# cc2510.net
KiCad netlist of a schematic drawn in Altium Designer
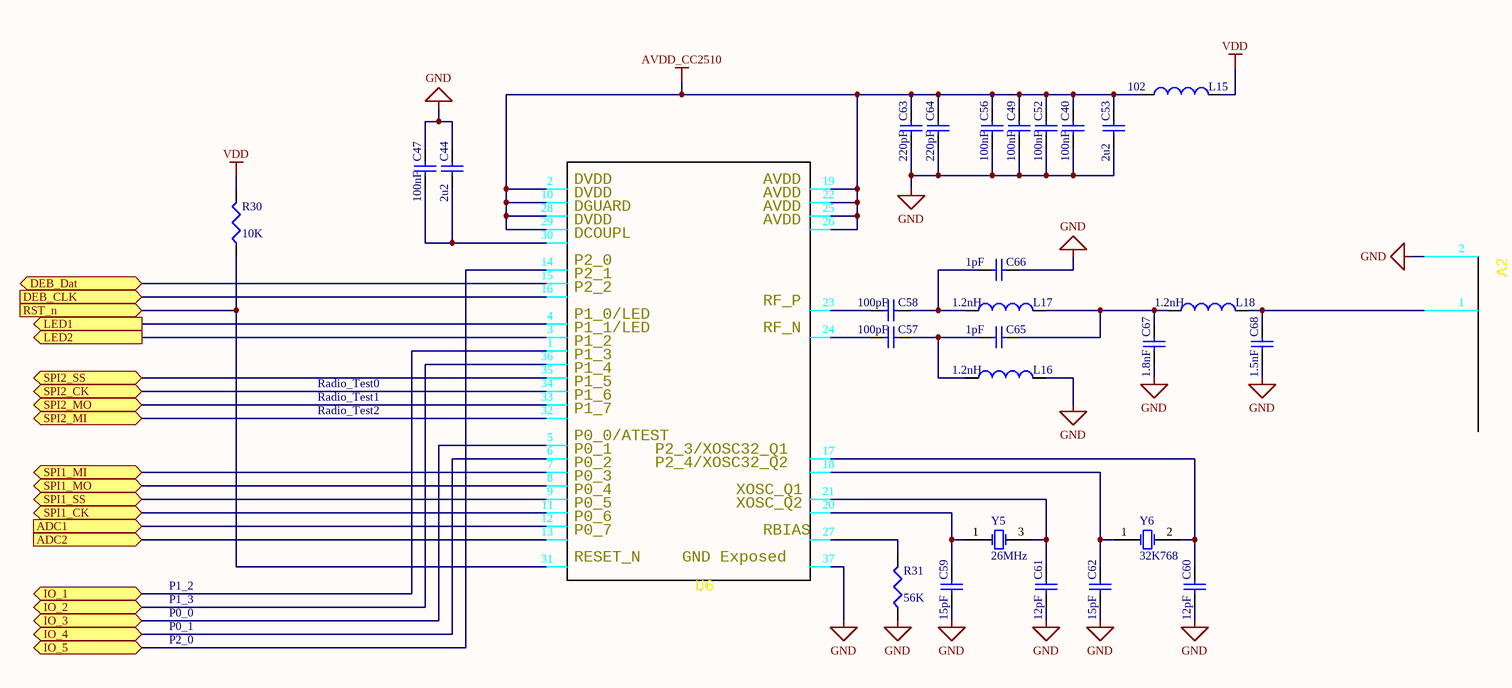
[diagram p0: cc2510.SchDoc]

(export (version "E")
  (design (tool "Eeschema 10.0.6"))
  (components
    (comp (ref "A2")
      (value "Antenna_IIFA_1")
      (footprint "antenna_IIFA_1")
      (description "Antenna single ended IIFA, 2450 MHz")
      (libsource (lib "mdap") (part "Antenna_IIFA_1"))
    )
    (comp (ref "C40")
      (value "100nF")
      (footprint "0402")
      (description "Capacitor")
      (fields
        (field (name "MANUFACTURER") "FARNELL")
        (field (name "Comment") "Cap")
        (field (name "PUBLISHER") "Altium Limited")
      )
      (libsource (lib "Miscellaneous Devices") (part "Cap"))
    )
    (comp (ref "C44")
      (value "2u2")
      (footprint "C0805")
      (description "Capacitor")
      (fields
        (field (name "MANUFACTURER") "FARNELL")
        (field (name "Comment") "Cap")
        (field (name "PUBLISHER") "Altium Limited")
      )
      (libsource (lib "Miscellaneous Devices") (part "Cap"))
    )
    (comp (ref "C47")
      (value "100nF")
      (footprint "0402")
      (description "Capacitor")
      (fields
        (field (name "MANUFACTURER") "FARNELL")
        (field (name "Comment") "Cap")
        (field (name "PUBLISHER") "Altium Limited")
      )
      (libsource (lib "Miscellaneous Devices") (part "Cap"))
    )
    (comp (ref "C49")
      (value "100nF")
      (footprint "0402")
      (description "Capacitor")
      (fields
        (field (name "MANUFACTURER") "FARNELL")
        (field (name "Comment") "Cap")
        (field (name "PUBLISHER") "Altium Limited")
      )
      (libsource (lib "Miscellaneous Devices") (part "Cap"))
    )
    (comp (ref "C52")
      (value "100nF")
      (footprint "0402")
      (description "Capacitor")
      (fields
        (field (name "MANUFACTURER") "FARNELL")
        (field (name "Comment") "Cap")
        (field (name "PUBLISHER") "Altium Limited")
      )
      (libsource (lib "Miscellaneous Devices") (part "Cap"))
    )
    (comp (ref "C53")
      (value "2u2")
      (footprint "C0805")
      (description "Capacitor")
      (fields
        (field (name "MANUFACTURER") "FARNELL")
        (field (name "Comment") "Cap")
        (field (name "PUBLISHER") "Altium Limited")
      )
      (libsource (lib "Miscellaneous Devices") (part "Cap"))
    )
    (comp (ref "C56")
      (value "100nF")
      (footprint "0402")
      (description "Capacitor")
      (fields
        (field (name "MANUFACTURER") "FARNELL")
        (field (name "Comment") "Cap")
        (field (name "PUBLISHER") "Altium Limited")
      )
      (libsource (lib "Miscellaneous Devices") (part "Cap"))
    )
    (comp (ref "C57")
      (value "100pF")
      (footprint "0402")
      (description "Capacitor")
      (fields
        (field (name "MANUFACTURER") "FARNELL")
        (field (name "Comment") "Cap")
        (field (name "PUBLISHER") "Altium Limited")
      )
      (libsource (lib "Miscellaneous Devices") (part "Cap"))
    )
    (comp (ref "C58")
      (value "100pF")
      (footprint "0402")
      (description "Capacitor")
      (fields
        (field (name "MANUFACTURER") "FARNELL")
        (field (name "Comment") "Cap")
        (field (name "PUBLISHER") "Altium Limited")
      )
      (libsource (lib "Miscellaneous Devices") (part "Cap"))
    )
    (comp (ref "C59")
      (value "15pF")
      (footprint "0402")
      (description "Capacitor")
      (fields
        (field (name "MANUFACTURER") "FARNELL")
        (field (name "Comment") "Cap")
        (field (name "PUBLISHER") "Altium Limited")
      )
      (libsource (lib "Miscellaneous Devices") (part "Cap"))
    )
    (comp (ref "C60")
      (value "12pF")
      (footprint "0402")
      (description "Capacitor")
      (fields
        (field (name "MANUFACTURER") "FARNELL")
        (field (name "Comment") "Cap")
        (field (name "PUBLISHER") "Altium Limited")
      )
      (libsource (lib "Miscellaneous Devices") (part "Cap"))
    )
    (comp (ref "C61")
      (value "12pF")
      (footprint "0402")
      (description "Capacitor")
      (fields
        (field (name "MANUFACTURER") "FARNELL")
        (field (name "Comment") "Cap")
        (field (name "PUBLISHER") "Altium Limited")
      )
      (libsource (lib "Miscellaneous Devices") (part "Cap"))
    )
    (comp (ref "C62")
      (value "15pF")
      (footprint "0402")
      (description "Capacitor")
      (fields
        (field (name "MANUFACTURER") "FARNELL")
        (field (name "Comment") "Cap")
        (field (name "PUBLISHER") "Altium Limited")
      )
      (libsource (lib "Miscellaneous Devices") (part "Cap"))
    )
    (comp (ref "C63")
      (value "220pF")
      (footprint "0402")
      (description "Capacitor")
      (fields
        (field (name "MANUFACTURER") "FARNELL")
        (field (name "Comment") "Cap")
        (field (name "PUBLISHER") "Altium Limited")
      )
      (libsource (lib "Miscellaneous Devices") (part "Cap"))
    )
    (comp (ref "C64")
      (value "220pF")
      (footprint "0402")
      (description "Capacitor")
      (fields
        (field (name "MANUFACTURER") "FARNELL")
        (field (name "Comment") "Cap")
        (field (name "PUBLISHER") "Altium Limited")
      )
      (libsource (lib "Miscellaneous Devices") (part "Cap"))
    )
    (comp (ref "C65")
      (value "1pF")
      (footprint "0402")
      (description "Capacitor")
      (fields
        (field (name "MANUFACTURER") "FARNELL")
        (field (name "Comment") "Cap")
        (field (name "PUBLISHER") "Altium Limited")
      )
      (libsource (lib "Miscellaneous Devices") (part "Cap"))
    )
    (comp (ref "C66")
      (value "1pF")
      (footprint "0402")
      (description "Capacitor")
      (fields
        (field (name "MANUFACTURER") "FARNELL")
        (field (name "Comment") "Cap")
        (field (name "PUBLISHER") "Altium Limited")
      )
      (libsource (lib "Miscellaneous Devices") (part "Cap"))
    )
    (comp (ref "C67")
      (value "1.8nF")
      (footprint "0402")
      (description "Capacitor")
      (fields
        (field (name "MANUFACTURER") "FARNELL")
        (field (name "Comment") "Cap")
        (field (name "PUBLISHER") "Altium Limited")
      )
      (libsource (lib "Miscellaneous Devices") (part "Cap"))
    )
    (comp (ref "C68")
      (value "1.5nF")
      (footprint "0402")
      (description "Capacitor")
      (fields
        (field (name "MANUFACTURER") "FARNELL")
        (field (name "Comment") "Cap")
        (field (name "PUBLISHER") "Altium Limited")
      )
      (libsource (lib "Miscellaneous Devices") (part "Cap"))
    )
    (comp (ref "L15")
      (value "102")
      (footprint "0402-A")
      (description "Inductor")
      (fields (field (name "MANUFACTURER") "FARNELL") (field (name "PUBLISHER") "Altium Limited"))
      (libsource (lib "Miscellaneous Devices") (part "Inductor"))
    )
    (comp (ref "L16")
      (value "1.2nH")
      (footprint "0402-A")
      (description "Inductor")
      (fields (field (name "MANUFACTURER") "FARNELL") (field (name "PUBLISHER") "Altium Limited"))
      (libsource (lib "Miscellaneous Devices") (part "Inductor"))
    )
    (comp (ref "L17")
      (value "1.2nH")
      (footprint "0402-A")
      (description "Inductor")
      (fields (field (name "MANUFACTURER") "FARNELL") (field (name "PUBLISHER") "Altium Limited"))
      (libsource (lib "Miscellaneous Devices") (part "Inductor"))
    )
    (comp (ref "L18")
      (value "1.2nH")
      (footprint "0402-A")
      (description "Inductor")
      (fields (field (name "MANUFACTURER") "FARNELL") (field (name "PUBLISHER") "Altium Limited"))
      (libsource (lib "Miscellaneous Devices") (part "Inductor"))
    )
    (comp (ref "R30")
      (value "10K")
      (footprint "J1-0603")
      (description "Resistor")
      (fields
        (field (name "MANUFACTURER") "FARNELL")
        (field (name "Comment") "Res3")
        (field (name "PUBLISHER") "Altium Limited")
      )
      (libsource (lib "Miscellaneous Devices") (part "Res3"))
    )
    (comp (ref "R31")
      (value "56K")
      (footprint "J1-0603")
      (description "Resistor")
      (fields
        (field (name "MANUFACTURER") "FARNELL")
        (field (name "Comment") "Res3")
        (field (name "PUBLISHER") "Altium Limited")
      )
      (libsource (lib "Miscellaneous Devices") (part "Res3"))
    )
    (comp (ref "U6")
      (value "CC2510")
      (footprint "QLP36_4_4 norteam silk (Reflow)")
      (description "Single chip transceiver")
      (fields (field (name "MANUFACTURER") "FARNELL"))
      (libsource (lib "mdap") (part "CC2510"))
    )
    (comp (ref "Y5")
      (value "26MHz")
      (footprint "xtal_3225")
      (description "Crystal Oscillator")
      (fields (field (name "MANUFACTURER") "Smart Prototyping"))
      (libsource (lib "MDAP") (part "XTAL_4"))
    )
    (comp (ref "Y6")
      (value "32K768")
      (footprint "xtal_3215")
      (description "Crystal Oscillator")
      (fields (field (name "MANUFACTURER") "Smart Prototyping"))
      (libsource (lib "Miscellaneous Devices") (part "XTAL"))
    )
  )
  (nets
    (net (code "1") (name "/ADC1") (class "Default") (node (ref "U6") (pin "12") (pintype "passive")))
    (net (code "2") (name "/ADC2") (class "Default") (node (ref "U6") (pin "13") (pintype "passive")))
    (net (code "3") (name "/DEB_CLK") (class "Default") (node (ref "U6") (pin "16") (pintype "passive")))
    (net (code "4") (name "/DEB_Dat") (class "Default") (node (ref "U6") (pin "15") (pintype "passive")))
    (net (code "5") (name "/IO_1") (class "Default") (node (ref "U6") (pin "1") (pintype "passive")))
    (net (code "6") (name "/IO_2") (class "Default") (node (ref "U6") (pin "36") (pintype "passive")))
    (net (code "7") (name "/IO_3") (class "Default") (node (ref "U6") (pin "5") (pintype "passive")))
    (net (code "8") (name "/IO_4") (class "Default") (node (ref "U6") (pin "6") (pintype "passive")))
    (net (code "9") (name "/IO_5") (class "Default") (node (ref "U6") (pin "14") (pintype "passive")))
    (net (code "10") (name "/LED1") (class "Default") (node (ref "U6") (pin "4") (pintype "passive")))
    (net (code "11") (name "/LED2") (class "Default") (node (ref "U6") (pin "3") (pintype "passive")))
    (net (code "12") (name "/RST_n") (class "Default")
      (node (ref "R30") (pin "1") (pinfunction "1_1") (pintype "passive"))
      (node (ref "U6") (pin "31") (pintype "passive"))
    )
    (net (code "13") (name "/SPI1_CK") (class "Default") (node (ref "U6") (pin "11") (pintype "passive")))
    (net (code "14") (name "/SPI1_MI") (class "Default") (node (ref "U6") (pin "7") (pintype "passive")))
    (net (code "15") (name "/SPI1_MO") (class "Default") (node (ref "U6") (pin "8") (pintype "passive")))
    (net (code "16") (name "/SPI1_SS") (class "Default") (node (ref "U6") (pin "9") (pintype "passive")))
    (net (code "17") (name "/SPI2_CK") (class "Default") (node (ref "U6") (pin "34") (pintype "passive")))
    (net (code "18") (name "/SPI2_MI") (class "Default") (node (ref "U6") (pin "32") (pintype "passive")))
    (net (code "19") (name "/SPI2_MO") (class "Default") (node (ref "U6") (pin "33") (pintype "passive")))
    (net (code "20") (name "/SPI2_SS") (class "Default") (node (ref "U6") (pin "35") (pintype "passive")))
    (net (code "21") (name "AVDD_CC2510") (class "Default")
      (node (ref "C40") (pin "2") (pinfunction "2_2") (pintype "passive"))
      (node (ref "C49") (pin "2") (pinfunction "2_2") (pintype "passive"))
      (node (ref "C52") (pin "2") (pinfunction "2_2") (pintype "passive"))
      (node (ref "C53") (pin "2") (pinfunction "2_2") (pintype "passive"))
      (node (ref "C56") (pin "2") (pinfunction "2_2") (pintype "passive"))
      (node (ref "C63") (pin "2") (pinfunction "2_2") (pintype "passive"))
      (node (ref "C64") (pin "2") (pinfunction "2_2") (pintype "passive"))
      (node (ref "L15") (pin "1") (pinfunction "1_1") (pintype "passive"))
      (node (ref "U6") (pin "10") (pintype "passive"))
      (node (ref "U6") (pin "19") (pintype "passive"))
      (node (ref "U6") (pin "2") (pintype "passive"))
      (node (ref "U6") (pin "22") (pintype "passive"))
      (node (ref "U6") (pin "25") (pintype "passive"))
      (node (ref "U6") (pin "26") (pintype "passive"))
      (node (ref "U6") (pin "28") (pintype "passive"))
      (node (ref "U6") (pin "29") (pintype "passive"))
    )
    (net (code "22") (name "GND") (class "Default")
      (node (ref "A2") (pin "2") (pintype "passive"))
      (node (ref "C40") (pin "1") (pinfunction "1_1") (pintype "passive"))
      (node (ref "C44") (pin "2") (pinfunction "2_2") (pintype "passive"))
      (node (ref "C47") (pin "2") (pinfunction "2_2") (pintype "passive"))
      (node (ref "C49") (pin "1") (pinfunction "1_1") (pintype "passive"))
      (node (ref "C52") (pin "1") (pinfunction "1_1") (pintype "passive"))
      (node (ref "C53") (pin "1") (pinfunction "1_1") (pintype "passive"))
      (node (ref "C56") (pin "1") (pinfunction "1_1") (pintype "passive"))
      (node (ref "C59") (pin "1") (pinfunction "1_1") (pintype "passive"))
      (node (ref "C60") (pin "1") (pinfunction "1_1") (pintype "passive"))
      (node (ref "C61") (pin "1") (pinfunction "1_1") (pintype "passive"))
      (node (ref "C62") (pin "1") (pinfunction "1_1") (pintype "passive"))
      (node (ref "C63") (pin "1") (pinfunction "1_1") (pintype "passive"))
      (node (ref "C64") (pin "1") (pinfunction "1_1") (pintype "passive"))
      (node (ref "C66") (pin "1") (pinfunction "1_1") (pintype "passive"))
      (node (ref "C67") (pin "1") (pinfunction "1_1") (pintype "passive"))
      (node (ref "C68") (pin "1") (pinfunction "1_1") (pintype "passive"))
      (node (ref "L16") (pin "2") (pinfunction "2_2") (pintype "passive"))
      (node (ref "R31") (pin "1") (pinfunction "1_1") (pintype "passive"))
      (node (ref "U6") (pin "37") (pintype "passive"))
    )
    (net (code "23") (name "Net-(A2-Pad1)") (class "Default")
      (node (ref "A2") (pin "1") (pintype "passive"))
      (node (ref "C68") (pin "2") (pinfunction "2_2") (pintype "passive"))
      (node (ref "L18") (pin "2") (pinfunction "2_2") (pintype "passive"))
    )
    (net (code "24") (name "Net-(C44-Pad1)") (class "Default")
      (node (ref "C44") (pin "1") (pinfunction "1_1") (pintype "passive"))
      (node (ref "C47") (pin "1") (pinfunction "1_1") (pintype "passive"))
      (node (ref "U6") (pin "30") (pintype "passive"))
    )
    (net (code "25") (name "Net-(C57-Pad1)") (class "Default")
      (node (ref "C57") (pin "1") (pinfunction "1_1") (pintype "passive"))
      (node (ref "C65") (pin "2") (pinfunction "2_2") (pintype "passive"))
      (node (ref "L16") (pin "1") (pinfunction "1_1") (pintype "passive"))
    )
    (net (code "26") (name "Net-(C57-Pad2)") (class "Default")
      (node (ref "C57") (pin "2") (pinfunction "2_2") (pintype "passive"))
      (node (ref "U6") (pin "24") (pintype "passive"))
    )
    (net (code "27") (name "Net-(C58-Pad1)") (class "Default")
      (node (ref "C58") (pin "1") (pinfunction "1_1") (pintype "passive"))
      (node (ref "C66") (pin "2") (pinfunction "2_2") (pintype "passive"))
      (node (ref "L17") (pin "1") (pinfunction "1_1") (pintype "passive"))
    )
    (net (code "28") (name "Net-(C58-Pad2)") (class "Default")
      (node (ref "C58") (pin "2") (pinfunction "2_2") (pintype "passive"))
      (node (ref "U6") (pin "23") (pintype "passive"))
    )
    (net (code "29") (name "Net-(C65-Pad1)") (class "Default")
      (node (ref "C65") (pin "1") (pinfunction "1_1") (pintype "passive"))
      (node (ref "C67") (pin "2") (pinfunction "2_2") (pintype "passive"))
      (node (ref "L17") (pin "2") (pinfunction "2_2") (pintype "passive"))
      (node (ref "L18") (pin "1") (pinfunction "1_1") (pintype "passive"))
    )
    (net (code "30") (name "Net-(R31-Pad2)") (class "Default")
      (node (ref "R31") (pin "2") (pinfunction "2_2") (pintype "passive"))
      (node (ref "U6") (pin "27") (pintype "passive"))
    )
    (net (code "31") (name "Net-(Y5-OSC1)") (class "Default")
      (node (ref "C59") (pin "2") (pinfunction "2_2") (pintype "passive"))
      (node (ref "U6") (pin "20") (pintype "passive"))
      (node (ref "Y5") (pin "1") (pinfunction "OSC1_1") (pintype "passive"))
    )
    (net (code "32") (name "Net-(Y5-OSC2)") (class "Default")
      (node (ref "C61") (pin "2") (pinfunction "2_2") (pintype "passive"))
      (node (ref "U6") (pin "21") (pintype "passive"))
      (node (ref "Y5") (pin "3") (pinfunction "OSC2_3") (pintype "passive"))
    )
    (net (code "33") (name "Net-(Y6-OSC1)") (class "Default")
      (node (ref "C62") (pin "2") (pinfunction "2_2") (pintype "passive"))
      (node (ref "U6") (pin "18") (pintype "passive"))
      (node (ref "Y6") (pin "1") (pinfunction "OSC1_1") (pintype "passive"))
    )
    (net (code "34") (name "Net-(Y6-OSC2)") (class "Default")
      (node (ref "C60") (pin "2") (pinfunction "2_2") (pintype "passive"))
      (node (ref "U6") (pin "17") (pintype "passive"))
      (node (ref "Y6") (pin "2") (pinfunction "OSC2_2") (pintype "passive"))
    )
    (net (code "35") (name "VDD") (class "Default")
      (node (ref "L15") (pin "2") (pinfunction "2_2") (pintype "passive"))
      (node (ref "R30") (pin "2") (pinfunction "2_2") (pintype "passive"))
    )
  )
)
